# test_parts.net
KiCad netlist of a schematic drawn in EAGLE
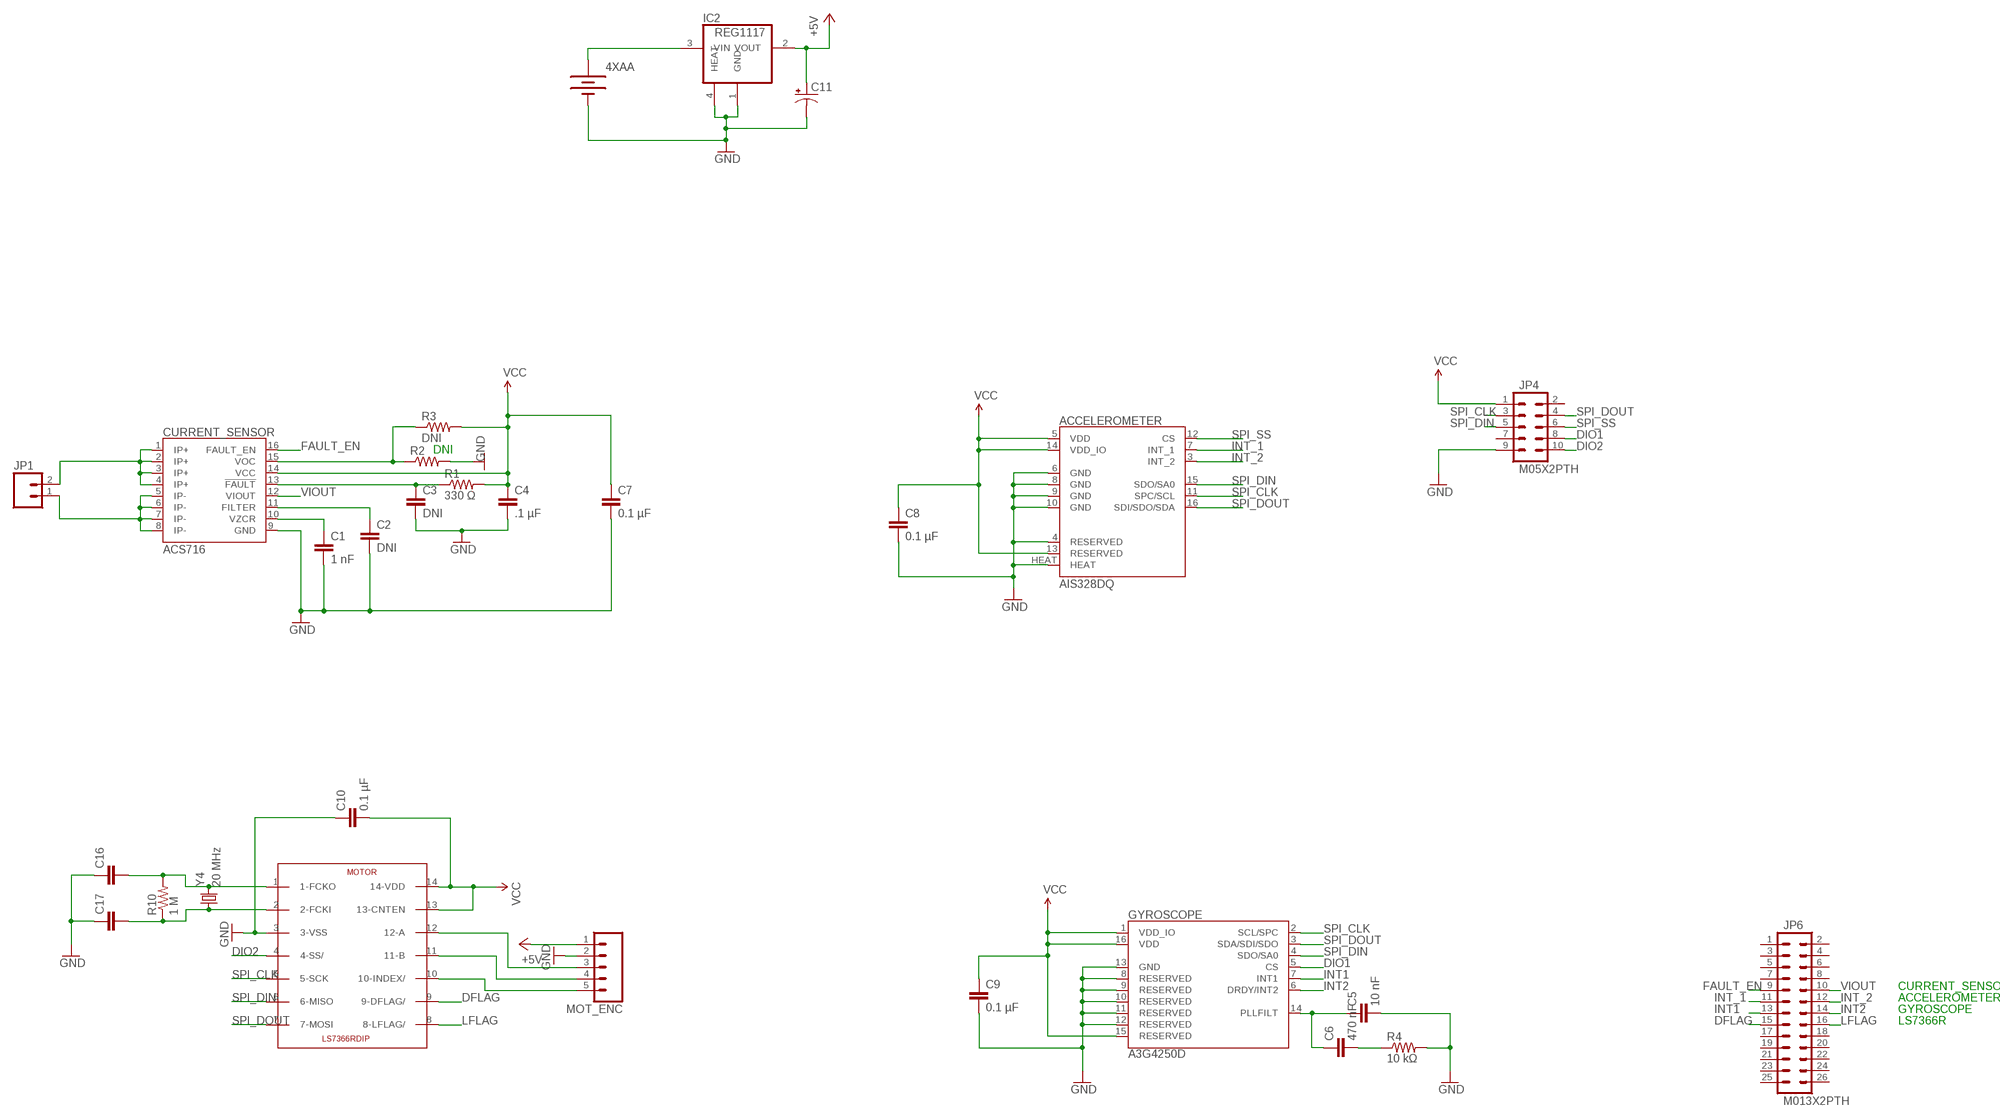
[diagram p0: schematic, sheet 1]

(export (version "E")
  (design (tool "Eeschema 10.0.6"))
  (components
    (comp (ref "4XAA")
      (value "BATTERYTOP")
      (footprint "eagle-import:BH4AA-PC")
      (libsource (lib "eagle-import") (part "BATTERYTOP"))
    )
    (comp (ref "ACCELEROMETER")
      (value "AIS328DQ")
      (footprint "eagle-import:QFPN-24")
      (libsource (lib "eagle-import") (part "AIS328DQQFPN-24"))
    )
    (comp (ref "C1")
      (value "1 nF")
      (footprint "eagle-import:0603-CAP")
      (libsource (lib "eagle-import") (part "CAP0603-CAP"))
    )
    (comp (ref "C2")
      (value "DNI")
      (footprint "eagle-import:0603-CAP")
      (libsource (lib "eagle-import") (part "CAP0603-CAP"))
    )
    (comp (ref "C3")
      (value "DNI")
      (footprint "eagle-import:0603-CAP")
      (libsource (lib "eagle-import") (part "CAP0603-CAP"))
    )
    (comp (ref "C4")
      (value ".1 µF")
      (footprint "eagle-import:0603-CAP")
      (libsource (lib "eagle-import") (part "CAP0603-CAP"))
    )
    (comp (ref "C5")
      (value "10 nF")
      (footprint "eagle-import:0603-CAP")
      (libsource (lib "eagle-import") (part "CAP0603-CAP"))
    )
    (comp (ref "C6")
      (value "470 nF")
      (footprint "eagle-import:0603-CAP")
      (libsource (lib "eagle-import") (part "CAP0603-CAP"))
    )
    (comp (ref "C7")
      (value "0.1 µF")
      (footprint "eagle-import:0603-CAP")
      (libsource (lib "eagle-import") (part "CAP0603-CAP"))
    )
    (comp (ref "C8")
      (value "0.1 µF")
      (footprint "eagle-import:0603-CAP")
      (libsource (lib "eagle-import") (part "CAP0603-CAP"))
    )
    (comp (ref "C9")
      (value "0.1 µF")
      (footprint "eagle-import:0603-CAP")
      (libsource (lib "eagle-import") (part "CAP0603-CAP"))
    )
    (comp (ref "C10")
      (value "0.1 µF")
      (footprint "eagle-import:0603-CAP")
      (libsource (lib "eagle-import") (part "CAP0603-CAP"))
    )
    (comp (ref "C11")
      (value "CAP_POL0603")
      (footprint "eagle-import:0603-CAP")
      (libsource (lib "eagle-import") (part "CAP_POL0603"))
    )
    (comp (ref "C16")
      (value "CAP0603-CAP")
      (footprint "eagle-import:0603-CAP")
      (libsource (lib "eagle-import") (part "nick_nu32_pic32mx795_v1_CAP0603-CAP"))
    )
    (comp (ref "C17")
      (value "CAP0603-CAP")
      (footprint "eagle-import:0603-CAP")
      (libsource (lib "eagle-import") (part "nick_nu32_pic32mx795_v1_CAP0603-CAP"))
    )
    (comp (ref "CURRENT_SENSOR")
      (value "ACS716")
      (footprint "eagle-import:SOICW")
      (libsource (lib "eagle-import") (part "ACS716"))
    )
    (comp (ref "GYROSCOPE")
      (value "A3G4250D")
      (footprint "eagle-import:LGA-16")
      (libsource (lib "eagle-import") (part "A3G4250DLGA16"))
    )
    (comp (ref "IC2")
      (value "REG1117")
      (footprint "eagle-import:SOT223")
      (libsource (lib "eagle-import") (part "REG1117"))
    )
    (comp (ref "JP1")
      (value "M02PTH")
      (footprint "eagle-import:1X02")
      (libsource (lib "eagle-import") (part "M02PTH"))
    )
    (comp (ref "JP4")
      (value "M05X2PTH")
      (footprint "eagle-import:AVR_ICSP")
      (libsource (lib "eagle-import") (part "M05X2PTH"))
    )
    (comp (ref "JP6")
      (value "M013X2PTH")
      (footprint "eagle-import:AVR_ICSP")
      (libsource (lib "eagle-import") (part "M013X2PTH"))
    )
    (comp (ref "MOTOR")
      (value "LS7366RDIP")
      (footprint "eagle-import:DIL14")
      (libsource (lib "eagle-import") (part "LS7366RDIP"))
    )
    (comp (ref "MOT_ENC")
      (value "M05PTH")
      (footprint "eagle-import:1X05")
      (libsource (lib "eagle-import") (part "M05PTH"))
    )
    (comp (ref "R1")
      (value "330 Ω")
      (footprint "eagle-import:0603-RES")
      (libsource (lib "eagle-import") (part "RESISTOR0603-RES"))
    )
    (comp (ref "R2")
      (value "DNI")
      (footprint "eagle-import:0603-RES")
      (libsource (lib "eagle-import") (part "RESISTOR0603-RES"))
    )
    (comp (ref "R3")
      (value "DNI")
      (footprint "eagle-import:0603-RES")
      (libsource (lib "eagle-import") (part "RESISTOR0603-RES"))
    )
    (comp (ref "R4")
      (value "10 kΩ")
      (footprint "eagle-import:0603-RES")
      (libsource (lib "eagle-import") (part "RESISTOR0603-RES"))
    )
    (comp (ref "R10")
      (value "1 M")
      (footprint "eagle-import:R0603")
      (libsource (lib "eagle-import") (part "R-US_R0603"))
    )
    (comp (ref "Y4")
      (value "20 MHz")
      (footprint "eagle-import:HC49US")
      (libsource (lib "eagle-import") (part "CRYSTALHC49US"))
    )
  )
  (nets
    (net (code "1") (name "+5V") (class "Default")
      (node (ref "C11") (pin "1") (pinfunction "+_1") (pintype "passive"))
      (node (ref "IC2") (pin "2") (pinfunction "VOUT_2") (pintype "output"))
      (node (ref "MOT_ENC") (pin "1") (pinfunction "1_1") (pintype "passive"))
    )
    (net (code "2") (name "/DFLAG") (class "Default")
      (node (ref "JP6") (pin "15") (pinfunction "15_15") (pintype "passive"))
      (node (ref "MOTOR") (pin "9") (pinfunction "9-DFLAG/_9") (pintype "bidirectional"))
    )
    (net (code "3") (name "/DIO1") (class "Default")
      (node (ref "GYROSCOPE") (pin "5") (pinfunction "CS_5") (pintype "bidirectional"))
      (node (ref "JP4") (pin "8") (pinfunction "8_8") (pintype "passive"))
    )
    (net (code "4") (name "/DIO2") (class "Default")
      (node (ref "JP4") (pin "10") (pinfunction "10_10") (pintype "passive"))
      (node (ref "MOTOR") (pin "4") (pinfunction "4-SS/_4") (pintype "bidirectional"))
    )
    (net (code "5") (name "/FAULT_EN") (class "Default")
      (node (ref "CURRENT_SENSOR") (pin "16") (pinfunction "FAULT_EN_16") (pintype "bidirectional"))
      (node (ref "JP6") (pin "9") (pinfunction "9_9") (pintype "passive"))
    )
    (net (code "6") (name "/INT1") (class "Default")
      (node (ref "GYROSCOPE") (pin "7") (pinfunction "INT1_7") (pintype "bidirectional"))
      (node (ref "JP6") (pin "13") (pinfunction "13_13") (pintype "passive"))
    )
    (net (code "7") (name "/INT2") (class "Default")
      (node (ref "GYROSCOPE") (pin "6") (pinfunction "DRDY/INT2_6") (pintype "bidirectional"))
      (node (ref "JP6") (pin "14") (pinfunction "14_14") (pintype "passive"))
    )
    (net (code "8") (name "/INT_1") (class "Default")
      (node (ref "ACCELEROMETER") (pin "7") (pinfunction "INT_1_7") (pintype "bidirectional"))
      (node (ref "JP6") (pin "11") (pinfunction "11_11") (pintype "passive"))
    )
    (net (code "9") (name "/INT_2") (class "Default")
      (node (ref "ACCELEROMETER") (pin "3") (pinfunction "INT_2_3") (pintype "bidirectional"))
      (node (ref "JP6") (pin "12") (pinfunction "12_12") (pintype "passive"))
    )
    (net (code "10") (name "/LFLAG") (class "Default")
      (node (ref "JP6") (pin "16") (pinfunction "16_16") (pintype "passive"))
      (node (ref "MOTOR") (pin "8") (pinfunction "8-LFLAG/_8") (pintype "bidirectional"))
    )
    (net (code "11") (name "/SPI_CLK") (class "Default")
      (node (ref "ACCELEROMETER") (pin "11") (pinfunction "SPC/SCL_11") (pintype "bidirectional"))
      (node (ref "GYROSCOPE") (pin "2") (pinfunction "SCL/SPC_2") (pintype "bidirectional"))
      (node (ref "JP4") (pin "3") (pinfunction "3_3") (pintype "passive"))
      (node (ref "MOTOR") (pin "5") (pinfunction "5-SCK_5") (pintype "bidirectional"))
    )
    (net (code "12") (name "/SPI_DIN") (class "Default")
      (node (ref "ACCELEROMETER") (pin "15") (pinfunction "SDO/SA0_15") (pintype "bidirectional"))
      (node (ref "GYROSCOPE") (pin "4") (pinfunction "SDO/SA0_4") (pintype "bidirectional"))
      (node (ref "JP4") (pin "5") (pinfunction "5_5") (pintype "passive"))
      (node (ref "MOTOR") (pin "6") (pinfunction "6-MISO_6") (pintype "bidirectional"))
    )
    (net (code "13") (name "/SPI_DOUT") (class "Default")
      (node (ref "ACCELEROMETER") (pin "16") (pinfunction "SDI/SDO/SDA_16") (pintype "bidirectional"))
      (node (ref "GYROSCOPE") (pin "3") (pinfunction "SDA/SDI/SDO_3") (pintype "bidirectional"))
      (node (ref "JP4") (pin "4") (pinfunction "4_4") (pintype "passive"))
      (node (ref "MOTOR") (pin "7") (pinfunction "7-MOSI_7") (pintype "bidirectional"))
    )
    (net (code "14") (name "/SPI_SS") (class "Default")
      (node (ref "ACCELEROMETER") (pin "12") (pinfunction "CS_12") (pintype "bidirectional"))
      (node (ref "JP4") (pin "6") (pinfunction "6_6") (pintype "passive"))
    )
    (net (code "15") (name "/VIOUT") (class "Default")
      (node (ref "CURRENT_SENSOR") (pin "12") (pinfunction "VIOUT_12") (pintype "bidirectional"))
      (node (ref "JP6") (pin "10") (pinfunction "10_10") (pintype "passive"))
    )
    (net (code "16") (name "GND") (class "Default")
      (node (ref "4XAA") (pin "-") (pinfunction "-_-") (pintype "power_in"))
      (node (ref "ACCELEROMETER") (pin "10") (pinfunction "GND_10") (pintype "bidirectional"))
      (node (ref "ACCELEROMETER") (pin "4") (pinfunction "RESERVED_4") (pintype "bidirectional"))
      (node (ref "ACCELEROMETER") (pin "6") (pinfunction "GND_6") (pintype "bidirectional"))
      (node (ref "ACCELEROMETER") (pin "8") (pinfunction "GND_8") (pintype "bidirectional"))
      (node (ref "ACCELEROMETER") (pin "9") (pinfunction "GND_9") (pintype "bidirectional"))
      (node (ref "ACCELEROMETER") (pin "HEAT") (pinfunction "HEAT_HEAT") (pintype "bidirectional"))
      (node (ref "C1") (pin "2") (pinfunction "2_2") (pintype "passive"))
      (node (ref "C10") (pin "1") (pinfunction "1_1") (pintype "passive"))
      (node (ref "C11") (pin "2") (pinfunction "-_2") (pintype "passive"))
      (node (ref "C16") (pin "1") (pinfunction "1_1") (pintype "passive"))
      (node (ref "C17") (pin "1") (pinfunction "1_1") (pintype "passive"))
      (node (ref "C2") (pin "2") (pinfunction "2_2") (pintype "passive"))
      (node (ref "C3") (pin "2") (pinfunction "2_2") (pintype "passive"))
      (node (ref "C4") (pin "2") (pinfunction "2_2") (pintype "passive"))
      (node (ref "C5") (pin "2") (pinfunction "2_2") (pintype "passive"))
      (node (ref "C7") (pin "2") (pinfunction "2_2") (pintype "passive"))
      (node (ref "C8") (pin "2") (pinfunction "2_2") (pintype "passive"))
      (node (ref "C9") (pin "2") (pinfunction "2_2") (pintype "passive"))
      (node (ref "CURRENT_SENSOR") (pin "9") (pinfunction "GND_9") (pintype "bidirectional"))
      (node (ref "GYROSCOPE") (pin "10") (pinfunction "RESERVED_10") (pintype "bidirectional"))
      (node (ref "GYROSCOPE") (pin "11") (pinfunction "RESERVED_11") (pintype "bidirectional"))
      (node (ref "GYROSCOPE") (pin "12") (pinfunction "RESERVED_12") (pintype "bidirectional"))
      (node (ref "GYROSCOPE") (pin "13") (pinfunction "GND_13") (pintype "bidirectional"))
      (node (ref "GYROSCOPE") (pin "8") (pinfunction "RESERVED_8") (pintype "bidirectional"))
      (node (ref "GYROSCOPE") (pin "9") (pinfunction "RESERVED_9") (pintype "bidirectional"))
      (node (ref "IC2") (pin "1") (pinfunction "GND_1") (pintype "power_in"))
      (node (ref "IC2") (pin "4") (pinfunction "HEAT_4") (pintype "bidirectional"))
      (node (ref "JP4") (pin "9") (pinfunction "9_9") (pintype "passive"))
      (node (ref "MOTOR") (pin "3") (pinfunction "3-VSS_3") (pintype "bidirectional"))
      (node (ref "MOT_ENC") (pin "2") (pinfunction "2_2") (pintype "passive"))
      (node (ref "R2") (pin "2") (pinfunction "2_2") (pintype "passive"))
      (node (ref "R4") (pin "2") (pinfunction "2_2") (pintype "passive"))
    )
    (net (code "17") (name "Net-(C6-Pad2)") (class "Default")
      (node (ref "C6") (pin "2") (pinfunction "2_2") (pintype "passive"))
      (node (ref "R4") (pin "1") (pinfunction "1_1") (pintype "passive"))
    )
    (net (code "18") (name "Net-(CURRENT_SENSOR-FILTER)") (class "Default")
      (node (ref "C2") (pin "1") (pinfunction "1_1") (pintype "passive"))
      (node (ref "CURRENT_SENSOR") (pin "11") (pinfunction "FILTER_11") (pintype "bidirectional"))
    )
    (net (code "19") (name "Net-(CURRENT_SENSOR-IP+-Pad1)") (class "Default")
      (node (ref "CURRENT_SENSOR") (pin "1") (pinfunction "IP+_1") (pintype "bidirectional"))
      (node (ref "CURRENT_SENSOR") (pin "2") (pinfunction "IP+_2") (pintype "bidirectional"))
      (node (ref "CURRENT_SENSOR") (pin "3") (pinfunction "IP+_3") (pintype "bidirectional"))
      (node (ref "CURRENT_SENSOR") (pin "4") (pinfunction "IP+_4") (pintype "bidirectional"))
      (node (ref "JP1") (pin "2") (pinfunction "2_2") (pintype "passive"))
    )
    (net (code "20") (name "Net-(CURRENT_SENSOR-IP--Pad5)") (class "Default")
      (node (ref "CURRENT_SENSOR") (pin "5") (pinfunction "IP-_5") (pintype "bidirectional"))
      (node (ref "CURRENT_SENSOR") (pin "6") (pinfunction "IP-_6") (pintype "bidirectional"))
      (node (ref "CURRENT_SENSOR") (pin "7") (pinfunction "IP-_7") (pintype "bidirectional"))
      (node (ref "CURRENT_SENSOR") (pin "8") (pinfunction "IP-_8") (pintype "bidirectional"))
      (node (ref "JP1") (pin "1") (pinfunction "1_1") (pintype "passive"))
    )
    (net (code "21") (name "Net-(CURRENT_SENSOR-VOC)") (class "Default")
      (node (ref "CURRENT_SENSOR") (pin "15") (pinfunction "VOC_15") (pintype "bidirectional"))
      (node (ref "R2") (pin "1") (pinfunction "1_1") (pintype "passive"))
      (node (ref "R3") (pin "1") (pinfunction "1_1") (pintype "passive"))
    )
    (net (code "22") (name "Net-(CURRENT_SENSOR-VZCR)") (class "Default")
      (node (ref "C1") (pin "1") (pinfunction "1_1") (pintype "passive"))
      (node (ref "CURRENT_SENSOR") (pin "10") (pinfunction "VZCR_10") (pintype "bidirectional"))
    )
    (net (code "23") (name "Net-(CURRENT_SENSOR-~{FAULT})") (class "Default")
      (node (ref "C3") (pin "1") (pinfunction "1_1") (pintype "passive"))
      (node (ref "CURRENT_SENSOR") (pin "13") (pinfunction "~{FAULT}_13") (pintype "bidirectional"))
      (node (ref "R1") (pin "1") (pinfunction "1_1") (pintype "passive"))
    )
    (net (code "24") (name "Net-(GYROSCOPE-PLLFILT)") (class "Default")
      (node (ref "C5") (pin "1") (pinfunction "1_1") (pintype "passive"))
      (node (ref "C6") (pin "1") (pinfunction "1_1") (pintype "passive"))
      (node (ref "GYROSCOPE") (pin "14") (pinfunction "PLLFILT_14") (pintype "bidirectional"))
    )
    (net (code "25") (name "Net-(IC2-VIN)") (class "Default")
      (node (ref "4XAA") (pin "+") (pinfunction "+_+") (pintype "power_in"))
      (node (ref "IC2") (pin "3") (pinfunction "VIN_3") (pintype "input"))
    )
    (net (code "26") (name "Net-(MOTOR-1-FCKO)") (class "Default")
      (node (ref "C16") (pin "2") (pinfunction "2_2") (pintype "passive"))
      (node (ref "MOTOR") (pin "1") (pinfunction "1-FCKO_1") (pintype "bidirectional"))
      (node (ref "R10") (pin "2") (pinfunction "2_2") (pintype "passive"))
      (node (ref "Y4") (pin "2") (pinfunction "2_2") (pintype "passive"))
    )
    (net (code "27") (name "Net-(MOTOR-2-FCKI)") (class "Default")
      (node (ref "C17") (pin "2") (pinfunction "2_2") (pintype "passive"))
      (node (ref "MOTOR") (pin "2") (pinfunction "2-FCKI_2") (pintype "bidirectional"))
      (node (ref "R10") (pin "1") (pinfunction "1_1") (pintype "passive"))
      (node (ref "Y4") (pin "1") (pinfunction "1_1") (pintype "passive"))
    )
    (net (code "28") (name "Net-(MOTOR-10-INDEX{slash})") (class "Default")
      (node (ref "MOTOR") (pin "10") (pinfunction "10-INDEX/_10") (pintype "bidirectional"))
      (node (ref "MOT_ENC") (pin "5") (pinfunction "5_5") (pintype "passive"))
    )
    (net (code "29") (name "Net-(MOTOR-11-B)") (class "Default")
      (node (ref "MOTOR") (pin "11") (pinfunction "11-B_11") (pintype "bidirectional"))
      (node (ref "MOT_ENC") (pin "4") (pinfunction "4_4") (pintype "passive"))
    )
    (net (code "30") (name "Net-(MOTOR-12-A)") (class "Default")
      (node (ref "MOTOR") (pin "12") (pinfunction "12-A_12") (pintype "bidirectional"))
      (node (ref "MOT_ENC") (pin "3") (pinfunction "3_3") (pintype "passive"))
    )
    (net (code "31") (name "VCC") (class "Default")
      (node (ref "ACCELEROMETER") (pin "13") (pinfunction "RESERVED_13") (pintype "bidirectional"))
      (node (ref "ACCELEROMETER") (pin "14") (pinfunction "VDD_IO_14") (pintype "bidirectional"))
      (node (ref "ACCELEROMETER") (pin "5") (pinfunction "VDD_5") (pintype "bidirectional"))
      (node (ref "C10") (pin "2") (pinfunction "2_2") (pintype "passive"))
      (node (ref "C4") (pin "1") (pinfunction "1_1") (pintype "passive"))
      (node (ref "C7") (pin "1") (pinfunction "1_1") (pintype "passive"))
      (node (ref "C8") (pin "1") (pinfunction "1_1") (pintype "passive"))
      (node (ref "C9") (pin "1") (pinfunction "1_1") (pintype "passive"))
      (node (ref "CURRENT_SENSOR") (pin "14") (pinfunction "VCC_14") (pintype "bidirectional"))
      (node (ref "GYROSCOPE") (pin "1") (pinfunction "VDD_IO_1") (pintype "bidirectional"))
      (node (ref "GYROSCOPE") (pin "15") (pinfunction "RESERVED_15") (pintype "bidirectional"))
      (node (ref "GYROSCOPE") (pin "16") (pinfunction "VDD_16") (pintype "bidirectional"))
      (node (ref "JP4") (pin "1") (pinfunction "1_1") (pintype "passive"))
      (node (ref "MOTOR") (pin "13") (pinfunction "13-CNTEN_13") (pintype "bidirectional"))
      (node (ref "MOTOR") (pin "14") (pinfunction "14-VDD_14") (pintype "bidirectional"))
      (node (ref "R1") (pin "2") (pinfunction "2_2") (pintype "passive"))
      (node (ref "R3") (pin "2") (pinfunction "2_2") (pintype "passive"))
    )
    (net (code "32") (name "unconnected-(JP4-Pad2)") (class "Default")
      (node (ref "JP4") (pin "2") (pinfunction "2_2") (pintype "passive"))
    )
    (net (code "33") (name "unconnected-(JP4-Pad7)") (class "Default")
      (node (ref "JP4") (pin "7") (pinfunction "7_7") (pintype "passive"))
    )
    (net (code "34") (name "unconnected-(JP6-Pad1)") (class "Default")
      (node (ref "JP6") (pin "1") (pinfunction "1_1") (pintype "passive"))
    )
    (net (code "35") (name "unconnected-(JP6-Pad2)") (class "Default")
      (node (ref "JP6") (pin "2") (pinfunction "2_2") (pintype "passive"))
    )
    (net (code "36") (name "unconnected-(JP6-Pad3)") (class "Default")
      (node (ref "JP6") (pin "3") (pinfunction "3_3") (pintype "passive"))
    )
    (net (code "37") (name "unconnected-(JP6-Pad4)") (class "Default")
      (node (ref "JP6") (pin "4") (pinfunction "4_4") (pintype "passive"))
    )
    (net (code "38") (name "unconnected-(JP6-Pad5)") (class "Default")
      (node (ref "JP6") (pin "5") (pinfunction "5_5") (pintype "passive"))
    )
    (net (code "39") (name "unconnected-(JP6-Pad6)") (class "Default")
      (node (ref "JP6") (pin "6") (pinfunction "6_6") (pintype "passive"))
    )
    (net (code "40") (name "unconnected-(JP6-Pad7)") (class "Default")
      (node (ref "JP6") (pin "7") (pinfunction "7_7") (pintype "passive"))
    )
    (net (code "41") (name "unconnected-(JP6-Pad8)") (class "Default")
      (node (ref "JP6") (pin "8") (pinfunction "8_8") (pintype "passive"))
    )
    (net (code "42") (name "unconnected-(JP6-Pad17)") (class "Default")
      (node (ref "JP6") (pin "17") (pinfunction "17_17") (pintype "passive"))
    )
    (net (code "43") (name "unconnected-(JP6-Pad18)") (class "Default")
      (node (ref "JP6") (pin "18") (pinfunction "18_18") (pintype "passive"))
    )
    (net (code "44") (name "unconnected-(JP6-Pad19)") (class "Default")
      (node (ref "JP6") (pin "19") (pinfunction "19_19") (pintype "passive"))
    )
    (net (code "45") (name "unconnected-(JP6-Pad20)") (class "Default")
      (node (ref "JP6") (pin "20") (pinfunction "20_20") (pintype "passive"))
    )
    (net (code "46") (name "unconnected-(JP6-Pad21)") (class "Default")
      (node (ref "JP6") (pin "21") (pinfunction "21_21") (pintype "passive"))
    )
    (net (code "47") (name "unconnected-(JP6-Pad22)") (class "Default")
      (node (ref "JP6") (pin "22") (pinfunction "22_22") (pintype "passive"))
    )
    (net (code "48") (name "unconnected-(JP6-Pad23)") (class "Default")
      (node (ref "JP6") (pin "23") (pinfunction "23_23") (pintype "passive"))
    )
    (net (code "49") (name "unconnected-(JP6-Pad24)") (class "Default")
      (node (ref "JP6") (pin "24") (pinfunction "24_24") (pintype "passive"))
    )
    (net (code "50") (name "unconnected-(JP6-Pad25)") (class "Default")
      (node (ref "JP6") (pin "25") (pinfunction "25_25") (pintype "passive"))
    )
    (net (code "51") (name "unconnected-(JP6-Pad26)") (class "Default")
      (node (ref "JP6") (pin "26") (pinfunction "26_26") (pintype "passive"))
    )
  )
)
